# Top_Level.net
KiCad netlist of a schematic drawn in Altium Designer
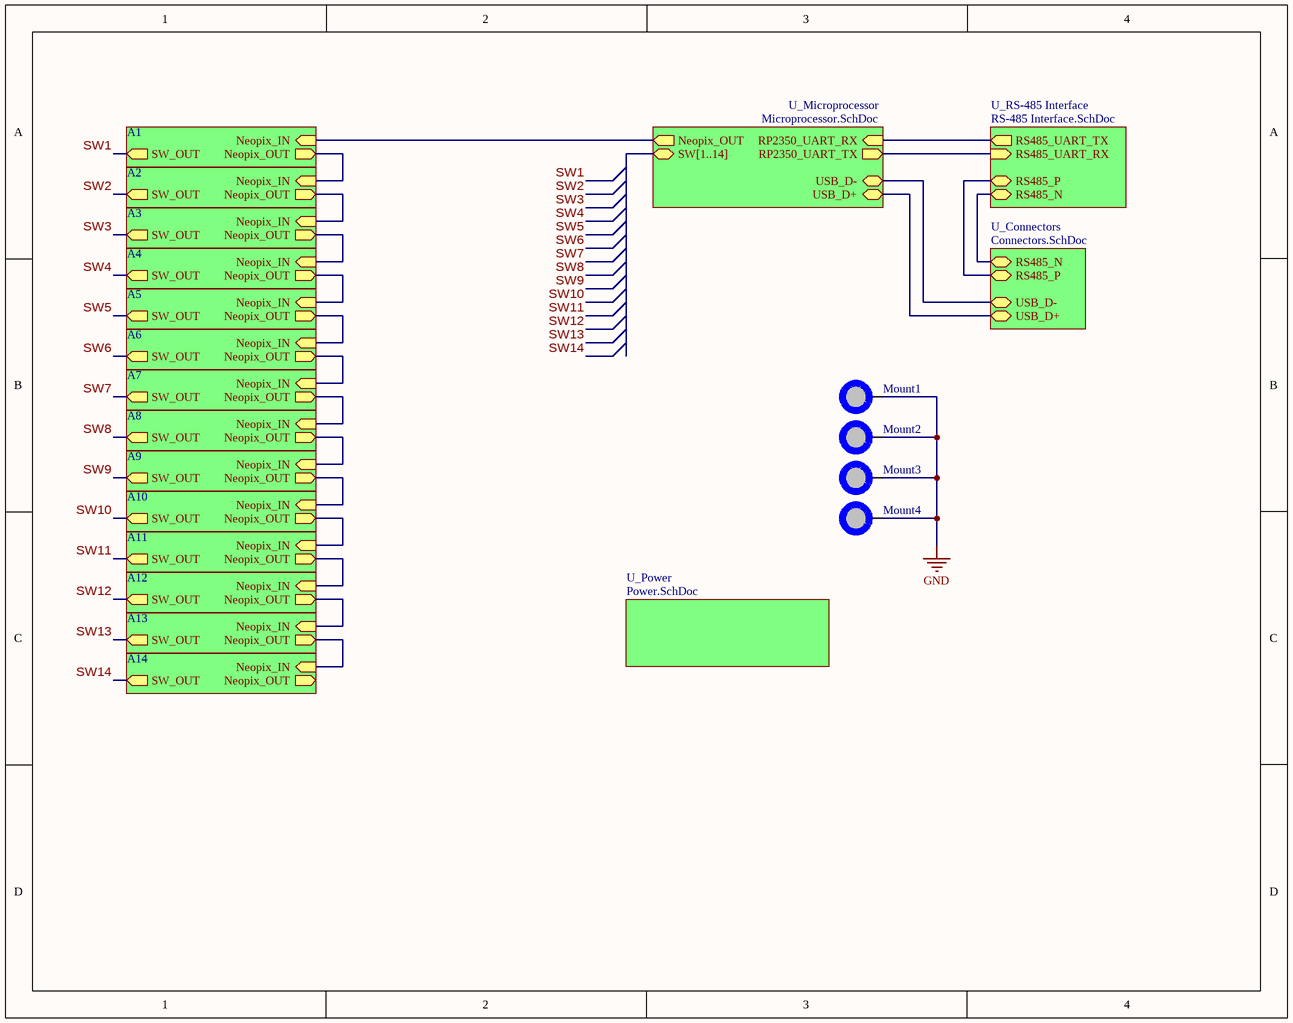
[diagram p0: Top Level.SchDoc]

(export (version "E")
  (design (tool "Eeschema 10.0.6"))
  (components
    (comp (ref "Mount1")
      (value "M3 Mount Hole")
      (footprint "[Mount] M3 Mount Hole")
      (description "Place at least 4.5mm from board edge. Plated.")
      (libsource (lib "Mounts, Pads, Vias") (part "[Mount] M3 Mount Hole"))
    )
    (comp (ref "Mount2")
      (value "M3 Mount Hole")
      (footprint "[Mount] M3 Mount Hole")
      (description "Place at least 4.5mm from board edge. Plated.")
      (libsource (lib "Mounts, Pads, Vias") (part "[Mount] M3 Mount Hole"))
    )
    (comp (ref "Mount3")
      (value "M3 Mount Hole")
      (footprint "[Mount] M3 Mount Hole")
      (description "Place at least 4.5mm from board edge. Plated.")
      (libsource (lib "Mounts, Pads, Vias") (part "[Mount] M3 Mount Hole"))
    )
    (comp (ref "Mount4")
      (value "M3 Mount Hole")
      (footprint "[Mount] M3 Mount Hole")
      (description "Place at least 4.5mm from board edge. Plated.")
      (libsource (lib "Mounts, Pads, Vias") (part "[Mount] M3 Mount Hole"))
    )
  )
  (nets
    (net (code "37") (name "GND") (class "Default")
      (node (ref "Mount1") (pin "1") (pintype "power_in"))
      (node (ref "Mount2") (pin "1") (pintype "power_in"))
      (node (ref "Mount3") (pin "1") (pintype "power_in"))
      (node (ref "Mount4") (pin "1") (pintype "power_in"))
    )
  )
)
